# MPPT.net
KiCad netlist of a schematic drawn in EAGLE
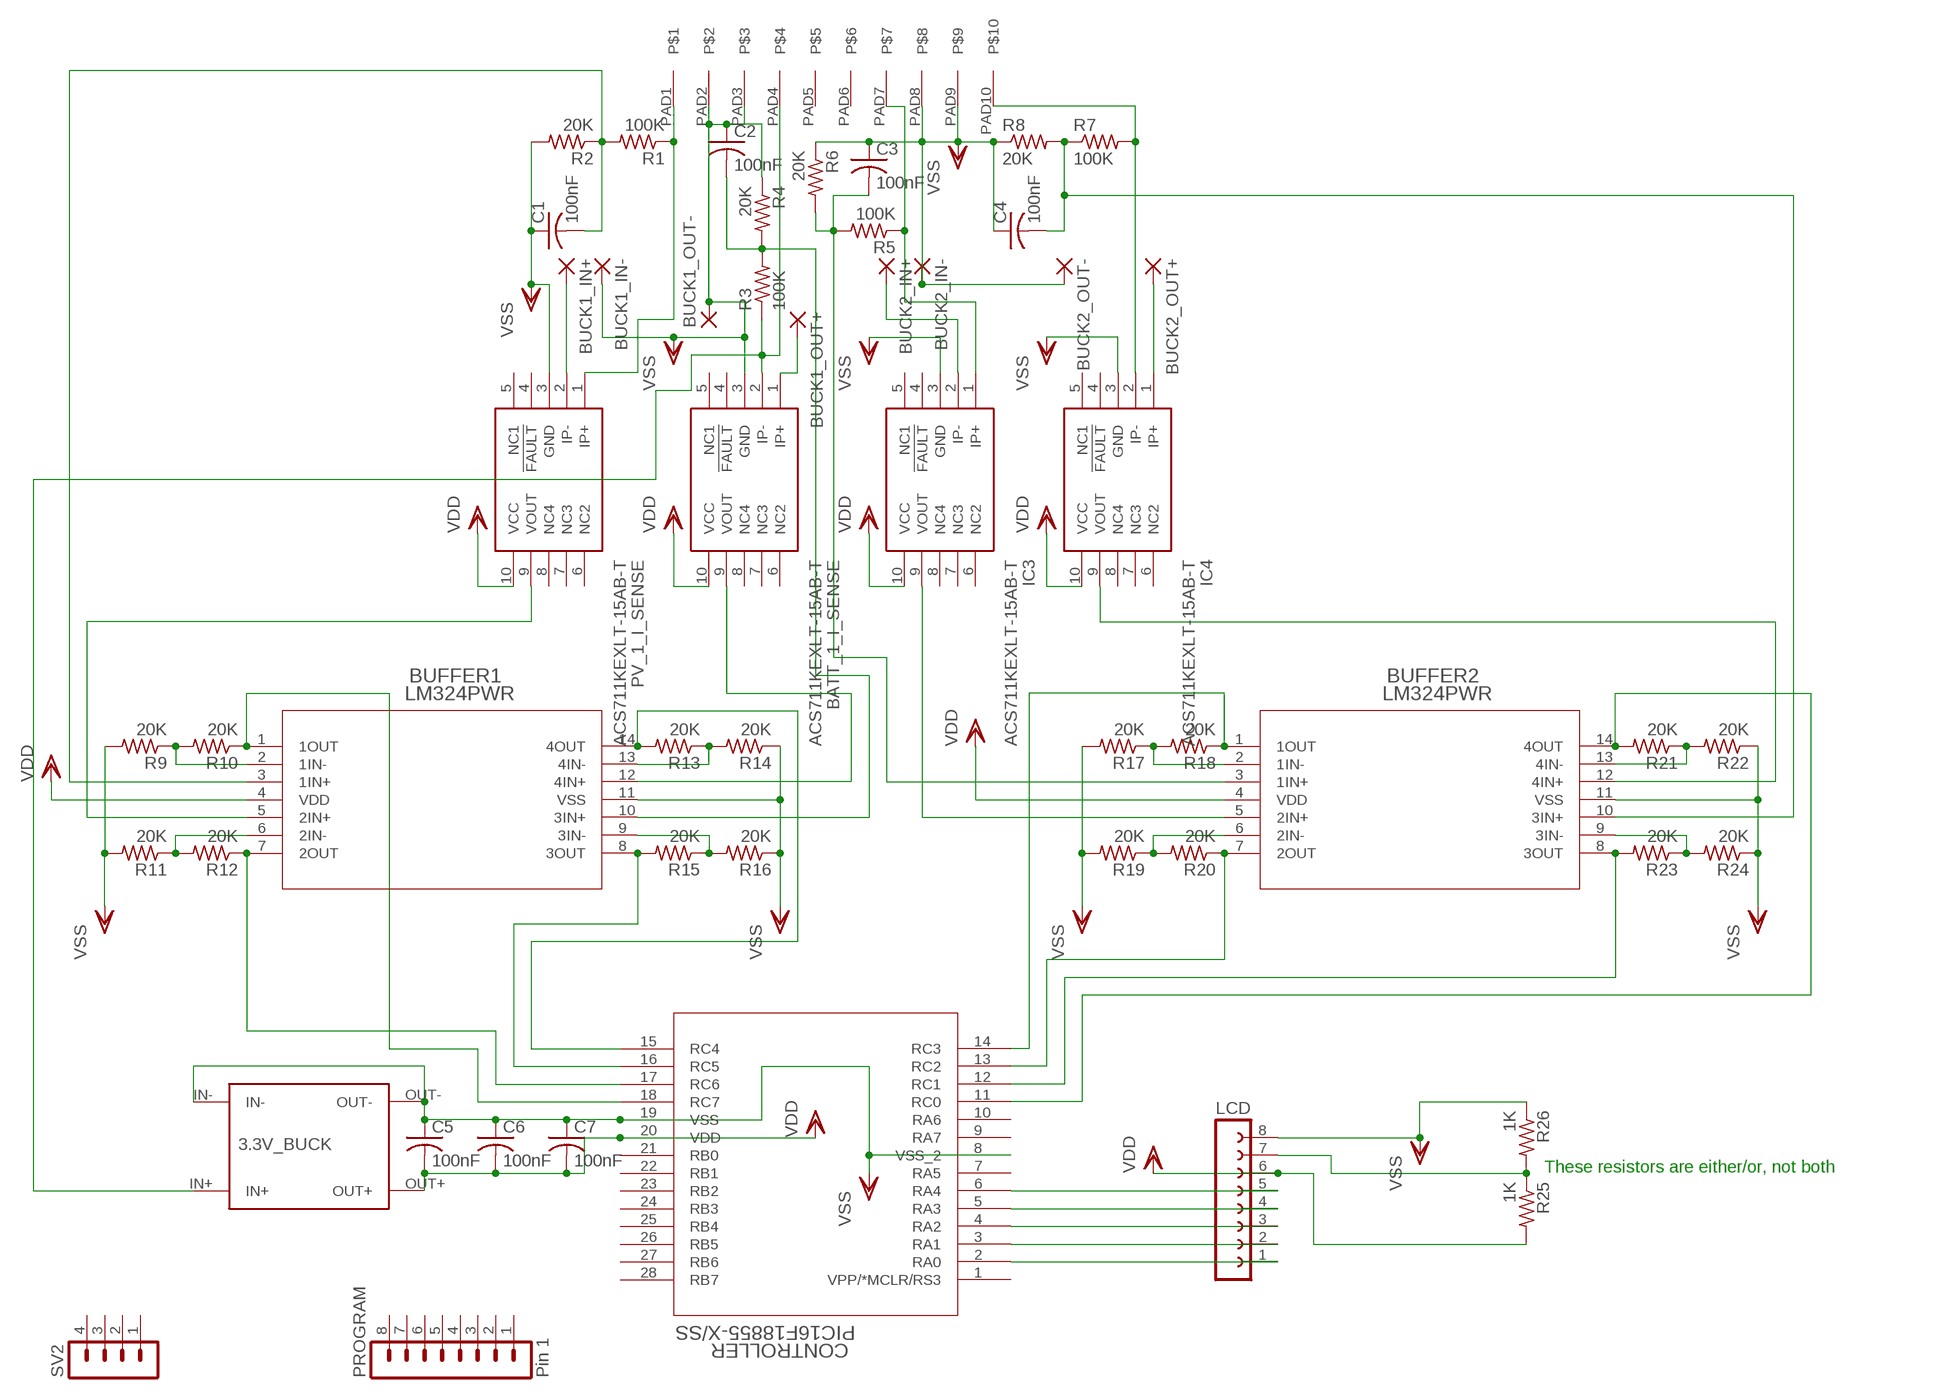
[diagram p0: schematic, sheet 1]

(export (version "E")
  (design (tool "Eeschema 10.0.6"))
  (components
    (comp (ref "3.3V_BUCK")
      (value "TINY_BUCK")
      (footprint "eagle-import:TINY_BUCK")
      (libsource (lib "eagle-import") (part "TINY_BUCK"))
    )
    (comp (ref "BATT_1_I_SENSE")
      (value "ACS711KEXLT-15AB-T")
      (footprint "eagle-import:EX-PACKAGE")
      (libsource (lib "eagle-import") (part "ACS711KEXLT-15AB-T"))
    )
    (comp (ref "BUCK1_IN+")
      (value "3,81/1,4")
      (footprint "eagle-import:3,81_1,4")
      (libsource (lib "eagle-import") (part "3,81/1,4"))
    )
    (comp (ref "BUCK1_IN-")
      (value "3,81/1,4")
      (footprint "eagle-import:3,81_1,4")
      (libsource (lib "eagle-import") (part "3,81/1,4"))
    )
    (comp (ref "BUCK1_OUT+")
      (value "3,81/1,4")
      (footprint "eagle-import:3,81_1,4")
      (libsource (lib "eagle-import") (part "3,81/1,4"))
    )
    (comp (ref "BUCK1_OUT-")
      (value "3,81/1,4")
      (footprint "eagle-import:3,81_1,4")
      (libsource (lib "eagle-import") (part "3,81/1,4"))
    )
    (comp (ref "BUCK2_IN+")
      (value "3,81/1,4")
      (footprint "eagle-import:3,81_1,4")
      (libsource (lib "eagle-import") (part "3,81/1,4"))
    )
    (comp (ref "BUCK2_IN-")
      (value "3,81/1,4")
      (footprint "eagle-import:3,81_1,4")
      (libsource (lib "eagle-import") (part "3,81/1,4"))
    )
    (comp (ref "BUCK2_OUT+")
      (value "3,81/1,4")
      (footprint "eagle-import:3,81_1,4")
      (libsource (lib "eagle-import") (part "3,81/1,4"))
    )
    (comp (ref "BUCK2_OUT-")
      (value "3,81/1,4")
      (footprint "eagle-import:3,81_1,4")
      (libsource (lib "eagle-import") (part "3,81/1,4"))
    )
    (comp (ref "BUFFER1")
      (value "LM324PWR")
      (footprint "eagle-import:PW14")
      (libsource (lib "eagle-import") (part "LM324PWR"))
    )
    (comp (ref "BUFFER2")
      (value "LM324PWR")
      (footprint "eagle-import:PW14")
      (libsource (lib "eagle-import") (part "LM324PWR"))
    )
    (comp (ref "C1")
      (value "100nF")
      (footprint "eagle-import:C0603")
      (libsource (lib "eagle-import") (part "C-USC0603"))
    )
    (comp (ref "C2")
      (value "100nF")
      (footprint "eagle-import:C0603")
      (libsource (lib "eagle-import") (part "C-USC0603"))
    )
    (comp (ref "C3")
      (value "100nF")
      (footprint "eagle-import:C0603")
      (libsource (lib "eagle-import") (part "C-USC0603"))
    )
    (comp (ref "C4")
      (value "100nF")
      (footprint "eagle-import:C0603")
      (libsource (lib "eagle-import") (part "C-USC0603"))
    )
    (comp (ref "C5")
      (value "100nF")
      (footprint "eagle-import:C0603")
      (libsource (lib "eagle-import") (part "C-USC0603"))
    )
    (comp (ref "C6")
      (value "100nF")
      (footprint "eagle-import:C0603")
      (libsource (lib "eagle-import") (part "C-USC0603"))
    )
    (comp (ref "C7")
      (value "100nF")
      (footprint "eagle-import:C0603")
      (libsource (lib "eagle-import") (part "C-USC0603"))
    )
    (comp (ref "CONTROLLER")
      (value "PIC16F18855-X/SS")
      (footprint "eagle-import:SSOP28_MC")
      (fields
        (field (name "MANUFACTURER_PART_NUMBER") "pic16f18855-x/ss")
        (field (name "COPYRIGHT") "Copyright (C) 2016 Accelerated Designs. All rights reserved")
      )
      (libsource (lib "eagle-import") (part "PIC16F18855-X/SS"))
    )
    (comp (ref "IC3")
      (value "ACS711KEXLT-15AB-T")
      (footprint "eagle-import:EX-PACKAGE")
      (libsource (lib "eagle-import") (part "ACS711KEXLT-15AB-T"))
    )
    (comp (ref "IC4")
      (value "ACS711KEXLT-15AB-T")
      (footprint "eagle-import:EX-PACKAGE")
      (libsource (lib "eagle-import") (part "ACS711KEXLT-15AB-T"))
    )
    (comp (ref "LCD")
      (value "FE08-1")
      (footprint "eagle-import:FE08")
      (libsource (lib "eagle-import") (part "FE08-1"))
    )
    (comp (ref "PROGRAM")
      (value "Pin 1")
      (footprint "eagle-import:MA08-1")
      (libsource (lib "eagle-import") (part "MA08-1"))
    )
    (comp (ref "PV_1_I_SENSE")
      (value "ACS711KEXLT-15AB-T")
      (footprint "eagle-import:EX-PACKAGE")
      (libsource (lib "eagle-import") (part "ACS711KEXLT-15AB-T"))
    )
    (comp (ref "R1")
      (value "100K")
      (footprint "eagle-import:R0603")
      (libsource (lib "eagle-import") (part "R-US_R0603"))
    )
    (comp (ref "R2")
      (value "20K")
      (footprint "eagle-import:R0603")
      (libsource (lib "eagle-import") (part "R-US_R0603"))
    )
    (comp (ref "R3")
      (value "100K")
      (footprint "eagle-import:R0603")
      (libsource (lib "eagle-import") (part "R-US_R0603"))
    )
    (comp (ref "R4")
      (value "20K")
      (footprint "eagle-import:R0603")
      (libsource (lib "eagle-import") (part "R-US_R0603"))
    )
    (comp (ref "R5")
      (value "100K")
      (footprint "eagle-import:R0603")
      (libsource (lib "eagle-import") (part "R-US_R0603"))
    )
    (comp (ref "R6")
      (value "20K")
      (footprint "eagle-import:R0603")
      (libsource (lib "eagle-import") (part "R-US_R0603"))
    )
    (comp (ref "R7")
      (value "100K")
      (footprint "eagle-import:R0603")
      (libsource (lib "eagle-import") (part "R-US_R0603"))
    )
    (comp (ref "R8")
      (value "20K")
      (footprint "eagle-import:R0603")
      (libsource (lib "eagle-import") (part "R-US_R0603"))
    )
    (comp (ref "R9")
      (value "20K")
      (footprint "eagle-import:R0603")
      (libsource (lib "eagle-import") (part "R-US_R0603"))
    )
    (comp (ref "R10")
      (value "20K")
      (footprint "eagle-import:R0603")
      (libsource (lib "eagle-import") (part "R-US_R0603"))
    )
    (comp (ref "R11")
      (value "20K")
      (footprint "eagle-import:R0603")
      (libsource (lib "eagle-import") (part "R-US_R0603"))
    )
    (comp (ref "R12")
      (value "20K")
      (footprint "eagle-import:R0603")
      (libsource (lib "eagle-import") (part "R-US_R0603"))
    )
    (comp (ref "R13")
      (value "20K")
      (footprint "eagle-import:R0603")
      (libsource (lib "eagle-import") (part "R-US_R0603"))
    )
    (comp (ref "R14")
      (value "20K")
      (footprint "eagle-import:R0603")
      (libsource (lib "eagle-import") (part "R-US_R0603"))
    )
    (comp (ref "R15")
      (value "20K")
      (footprint "eagle-import:R0603")
      (libsource (lib "eagle-import") (part "R-US_R0603"))
    )
    (comp (ref "R16")
      (value "20K")
      (footprint "eagle-import:R0603")
      (libsource (lib "eagle-import") (part "R-US_R0603"))
    )
    (comp (ref "R17")
      (value "20K")
      (footprint "eagle-import:R0603")
      (libsource (lib "eagle-import") (part "R-US_R0603"))
    )
    (comp (ref "R18")
      (value "20K")
      (footprint "eagle-import:R0603")
      (libsource (lib "eagle-import") (part "R-US_R0603"))
    )
    (comp (ref "R19")
      (value "20K")
      (footprint "eagle-import:R0603")
      (libsource (lib "eagle-import") (part "R-US_R0603"))
    )
    (comp (ref "R20")
      (value "20K")
      (footprint "eagle-import:R0603")
      (libsource (lib "eagle-import") (part "R-US_R0603"))
    )
    (comp (ref "R21")
      (value "20K")
      (footprint "eagle-import:R0603")
      (libsource (lib "eagle-import") (part "R-US_R0603"))
    )
    (comp (ref "R22")
      (value "20K")
      (footprint "eagle-import:R0603")
      (libsource (lib "eagle-import") (part "R-US_R0603"))
    )
    (comp (ref "R23")
      (value "20K")
      (footprint "eagle-import:R0603")
      (libsource (lib "eagle-import") (part "R-US_R0603"))
    )
    (comp (ref "R24")
      (value "20K")
      (footprint "eagle-import:R0603")
      (libsource (lib "eagle-import") (part "R-US_R0603"))
    )
    (comp (ref "R25")
      (value "1K")
      (footprint "eagle-import:R0603")
      (libsource (lib "eagle-import") (part "R-US_R0603"))
    )
    (comp (ref "R26")
      (value "1K")
      (footprint "eagle-import:R0603")
      (libsource (lib "eagle-import") (part "R-US_R0603"))
    )
    (comp (ref "SV2")
      (value "MA04-1")
      (footprint "eagle-import:MA04-1")
      (libsource (lib "eagle-import") (part "MA04-1"))
    )
    (comp (ref "U$1")
      (value "CONN-KF2EDG-10(5.08)E-BAYPLUGGABLECONNECTORS")
      (footprint "eagle-import:CONN-KF2EDG-10(5.08)")
      (libsource (lib "eagle-import") (part "CONN-KF2EDG-10(5.08)E-BAYPLUGGABLECONNECTORS"))
    )
  )
  (nets
    (net (code "1") (name "Net-(BATT_1_I_SENSE-IP+)") (class "Default")
      (node (ref "BATT_1_I_SENSE") (pin "1") (pinfunction "IP+_1") (pintype "bidirectional"))
      (node (ref "BUCK1_OUT+") (pin "1") (pinfunction "P_1") (pintype "passive"))
    )
    (net (code "2") (name "Net-(BATT_1_I_SENSE-IP-)") (class "Default")
      (node (ref "3.3V_BUCK") (pin "IN+") (pinfunction "IN+_IN+") (pintype "power_in"))
      (node (ref "BATT_1_I_SENSE") (pin "2") (pinfunction "IP-_2") (pintype "bidirectional"))
      (node (ref "R3") (pin "1") (pinfunction "1_1") (pintype "passive"))
      (node (ref "U$1") (pin "PAD4") (pinfunction "P$4_PAD4") (pintype "bidirectional"))
    )
    (net (code "3") (name "Net-(BATT_1_I_SENSE-VOUT)") (class "Default")
      (node (ref "BATT_1_I_SENSE") (pin "9") (pinfunction "VOUT_9") (pintype "bidirectional"))
      (node (ref "BUFFER1") (pin "12") (pinfunction "4IN+_12") (pintype "input"))
    )
    (net (code "4") (name "Net-(BUCK1_IN+-P)") (class "Default")
      (node (ref "BUCK1_IN+") (pin "1") (pinfunction "P_1") (pintype "passive"))
      (node (ref "PV_1_I_SENSE") (pin "2") (pinfunction "IP-_2") (pintype "bidirectional"))
    )
    (net (code "5") (name "Net-(BUCK2_IN+-P)") (class "Default")
      (node (ref "BUCK2_IN+") (pin "1") (pinfunction "P_1") (pintype "passive"))
      (node (ref "IC3") (pin "2") (pinfunction "IP-_2") (pintype "bidirectional"))
    )
    (net (code "6") (name "Net-(BUCK2_OUT+-P)") (class "Default")
      (node (ref "BUCK2_OUT+") (pin "1") (pinfunction "P_1") (pintype "passive"))
      (node (ref "IC4") (pin "1") (pinfunction "IP+_1") (pintype "bidirectional"))
    )
    (net (code "7") (name "Net-(BUFFER1-1IN+)") (class "Default")
      (node (ref "BUFFER1") (pin "3") (pinfunction "1IN+_3") (pintype "input"))
      (node (ref "C1") (pin "2") (pinfunction "2_2") (pintype "passive"))
      (node (ref "R1") (pin "2") (pinfunction "2_2") (pintype "passive"))
      (node (ref "R2") (pin "1") (pinfunction "1_1") (pintype "passive"))
    )
    (net (code "8") (name "Net-(BUFFER1-1IN-)") (class "Default")
      (node (ref "BUFFER1") (pin "2") (pinfunction "1IN-_2") (pintype "input"))
      (node (ref "R10") (pin "2") (pinfunction "2_2") (pintype "passive"))
      (node (ref "R9") (pin "1") (pinfunction "1_1") (pintype "passive"))
    )
    (net (code "9") (name "Net-(BUFFER1-1OUT)") (class "Default")
      (node (ref "BUFFER1") (pin "1") (pinfunction "1OUT_1") (pintype "output"))
      (node (ref "CONTROLLER") (pin "18") (pinfunction "RC7_18") (pintype "bidirectional"))
      (node (ref "R10") (pin "1") (pinfunction "1_1") (pintype "passive"))
    )
    (net (code "10") (name "Net-(BUFFER1-2IN+)") (class "Default")
      (node (ref "BUFFER1") (pin "5") (pinfunction "2IN+_5") (pintype "input"))
      (node (ref "PV_1_I_SENSE") (pin "9") (pinfunction "VOUT_9") (pintype "bidirectional"))
    )
    (net (code "11") (name "Net-(BUFFER1-2IN-)") (class "Default")
      (node (ref "BUFFER1") (pin "6") (pinfunction "2IN-_6") (pintype "input"))
      (node (ref "R11") (pin "1") (pinfunction "1_1") (pintype "passive"))
      (node (ref "R12") (pin "2") (pinfunction "2_2") (pintype "passive"))
    )
    (net (code "12") (name "Net-(BUFFER1-2OUT)") (class "Default")
      (node (ref "BUFFER1") (pin "7") (pinfunction "2OUT_7") (pintype "output"))
      (node (ref "CONTROLLER") (pin "17") (pinfunction "RC6_17") (pintype "bidirectional"))
      (node (ref "R12") (pin "1") (pinfunction "1_1") (pintype "passive"))
    )
    (net (code "13") (name "Net-(BUFFER1-3IN+)") (class "Default")
      (node (ref "BUFFER1") (pin "10") (pinfunction "3IN+_10") (pintype "input"))
      (node (ref "C2") (pin "2") (pinfunction "2_2") (pintype "passive"))
      (node (ref "R3") (pin "2") (pinfunction "2_2") (pintype "passive"))
      (node (ref "R4") (pin "2") (pinfunction "2_2") (pintype "passive"))
    )
    (net (code "14") (name "Net-(BUFFER1-3IN-)") (class "Default")
      (node (ref "BUFFER1") (pin "9") (pinfunction "3IN-_9") (pintype "input"))
      (node (ref "R15") (pin "1") (pinfunction "1_1") (pintype "passive"))
      (node (ref "R16") (pin "2") (pinfunction "2_2") (pintype "passive"))
    )
    (net (code "15") (name "Net-(BUFFER1-3OUT)") (class "Default")
      (node (ref "BUFFER1") (pin "8") (pinfunction "3OUT_8") (pintype "output"))
      (node (ref "CONTROLLER") (pin "16") (pinfunction "RC5_16") (pintype "bidirectional"))
      (node (ref "R15") (pin "2") (pinfunction "2_2") (pintype "passive"))
    )
    (net (code "16") (name "Net-(BUFFER1-4IN-)") (class "Default")
      (node (ref "BUFFER1") (pin "13") (pinfunction "4IN-_13") (pintype "input"))
      (node (ref "R13") (pin "1") (pinfunction "1_1") (pintype "passive"))
      (node (ref "R14") (pin "2") (pinfunction "2_2") (pintype "passive"))
    )
    (net (code "17") (name "Net-(BUFFER1-4OUT)") (class "Default")
      (node (ref "BUFFER1") (pin "14") (pinfunction "4OUT_14") (pintype "output"))
      (node (ref "CONTROLLER") (pin "15") (pinfunction "RC4_15") (pintype "bidirectional"))
      (node (ref "R13") (pin "2") (pinfunction "2_2") (pintype "passive"))
    )
    (net (code "18") (name "Net-(BUFFER2-1IN+)") (class "Default")
      (node (ref "BUFFER2") (pin "3") (pinfunction "1IN+_3") (pintype "input"))
      (node (ref "C3") (pin "2") (pinfunction "2_2") (pintype "passive"))
      (node (ref "R5") (pin "2") (pinfunction "2_2") (pintype "passive"))
      (node (ref "R6") (pin "2") (pinfunction "2_2") (pintype "passive"))
    )
    (net (code "19") (name "Net-(BUFFER2-1IN-)") (class "Default")
      (node (ref "BUFFER2") (pin "2") (pinfunction "1IN-_2") (pintype "input"))
      (node (ref "R17") (pin "1") (pinfunction "1_1") (pintype "passive"))
      (node (ref "R18") (pin "2") (pinfunction "2_2") (pintype "passive"))
    )
    (net (code "20") (name "Net-(BUFFER2-1OUT)") (class "Default")
      (node (ref "BUFFER2") (pin "1") (pinfunction "1OUT_1") (pintype "output"))
      (node (ref "CONTROLLER") (pin "14") (pinfunction "RC3_14") (pintype "bidirectional"))
      (node (ref "R18") (pin "1") (pinfunction "1_1") (pintype "passive"))
    )
    (net (code "21") (name "Net-(BUFFER2-2IN+)") (class "Default")
      (node (ref "BUFFER2") (pin "5") (pinfunction "2IN+_5") (pintype "input"))
      (node (ref "IC3") (pin "9") (pinfunction "VOUT_9") (pintype "bidirectional"))
    )
    (net (code "22") (name "Net-(BUFFER2-2IN-)") (class "Default")
      (node (ref "BUFFER2") (pin "6") (pinfunction "2IN-_6") (pintype "input"))
      (node (ref "R19") (pin "1") (pinfunction "1_1") (pintype "passive"))
      (node (ref "R20") (pin "2") (pinfunction "2_2") (pintype "passive"))
    )
    (net (code "23") (name "Net-(BUFFER2-2OUT)") (class "Default")
      (node (ref "BUFFER2") (pin "7") (pinfunction "2OUT_7") (pintype "output"))
      (node (ref "CONTROLLER") (pin "13") (pinfunction "RC2_13") (pintype "bidirectional"))
      (node (ref "R20") (pin "1") (pinfunction "1_1") (pintype "passive"))
    )
    (net (code "24") (name "Net-(BUFFER2-3IN+)") (class "Default")
      (node (ref "BUFFER2") (pin "10") (pinfunction "3IN+_10") (pintype "input"))
      (node (ref "C4") (pin "2") (pinfunction "2_2") (pintype "passive"))
      (node (ref "R7") (pin "1") (pinfunction "1_1") (pintype "passive"))
      (node (ref "R8") (pin "2") (pinfunction "2_2") (pintype "passive"))
    )
    (net (code "25") (name "Net-(BUFFER2-3IN-)") (class "Default")
      (node (ref "BUFFER2") (pin "9") (pinfunction "3IN-_9") (pintype "input"))
      (node (ref "R23") (pin "1") (pinfunction "1_1") (pintype "passive"))
      (node (ref "R24") (pin "2") (pinfunction "2_2") (pintype "passive"))
    )
    (net (code "26") (name "Net-(BUFFER2-3OUT)") (class "Default")
      (node (ref "BUFFER2") (pin "8") (pinfunction "3OUT_8") (pintype "output"))
      (node (ref "CONTROLLER") (pin "12") (pinfunction "RC1_12") (pintype "bidirectional"))
      (node (ref "R23") (pin "2") (pinfunction "2_2") (pintype "passive"))
    )
    (net (code "27") (name "Net-(BUFFER2-4IN+)") (class "Default")
      (node (ref "BUFFER2") (pin "12") (pinfunction "4IN+_12") (pintype "input"))
      (node (ref "IC4") (pin "9") (pinfunction "VOUT_9") (pintype "bidirectional"))
    )
    (net (code "28") (name "Net-(BUFFER2-4IN-)") (class "Default")
      (node (ref "BUFFER2") (pin "13") (pinfunction "4IN-_13") (pintype "input"))
      (node (ref "R21") (pin "1") (pinfunction "1_1") (pintype "passive"))
      (node (ref "R22") (pin "2") (pinfunction "2_2") (pintype "passive"))
    )
    (net (code "29") (name "Net-(BUFFER2-4OUT)") (class "Default")
      (node (ref "BUFFER2") (pin "14") (pinfunction "4OUT_14") (pintype "output"))
      (node (ref "CONTROLLER") (pin "11") (pinfunction "RC0_11") (pintype "bidirectional"))
      (node (ref "R21") (pin "2") (pinfunction "2_2") (pintype "passive"))
    )
    (net (code "30") (name "Net-(CONTROLLER-RA0)") (class "Default")
      (node (ref "CONTROLLER") (pin "2") (pinfunction "RA0_2") (pintype "bidirectional"))
      (node (ref "LCD") (pin "1") (pinfunction "1_1") (pintype "passive"))
    )
    (net (code "31") (name "Net-(CONTROLLER-RA1)") (class "Default")
      (node (ref "CONTROLLER") (pin "3") (pinfunction "RA1_3") (pintype "bidirectional"))
      (node (ref "LCD") (pin "2") (pinfunction "2_2") (pintype "passive"))
    )
    (net (code "32") (name "Net-(CONTROLLER-RA2)") (class "Default")
      (node (ref "CONTROLLER") (pin "4") (pinfunction "RA2_4") (pintype "bidirectional"))
      (node (ref "LCD") (pin "3") (pinfunction "3_3") (pintype "passive"))
    )
    (net (code "33") (name "Net-(CONTROLLER-RA3)") (class "Default")
      (node (ref "CONTROLLER") (pin "5") (pinfunction "RA3_5") (pintype "bidirectional"))
      (node (ref "LCD") (pin "4") (pinfunction "4_4") (pintype "passive"))
    )
    (net (code "34") (name "Net-(CONTROLLER-RA4)") (class "Default")
      (node (ref "CONTROLLER") (pin "6") (pinfunction "RA4_6") (pintype "bidirectional"))
      (node (ref "LCD") (pin "5") (pinfunction "5_5") (pintype "passive"))
    )
    (net (code "35") (name "Net-(IC3-IP+)") (class "Default")
      (node (ref "IC3") (pin "1") (pinfunction "IP+_1") (pintype "bidirectional"))
      (node (ref "R5") (pin "1") (pinfunction "1_1") (pintype "passive"))
      (node (ref "U$1") (pin "PAD7") (pinfunction "P$7_PAD7") (pintype "bidirectional"))
    )
    (net (code "36") (name "Net-(IC4-IP-)") (class "Default")
      (node (ref "IC4") (pin "2") (pinfunction "IP-_2") (pintype "bidirectional"))
      (node (ref "R7") (pin "2") (pinfunction "2_2") (pintype "passive"))
      (node (ref "U$1") (pin "PAD10") (pinfunction "P$10_PAD10") (pintype "bidirectional"))
    )
    (net (code "37") (name "Net-(LCD-Pad7)") (class "Default")
      (node (ref "LCD") (pin "7") (pinfunction "7_7") (pintype "passive"))
      (node (ref "R25") (pin "1") (pinfunction "1_1") (pintype "passive"))
      (node (ref "R26") (pin "2") (pinfunction "2_2") (pintype "passive"))
    )
    (net (code "38") (name "Net-(PV_1_I_SENSE-IP+)") (class "Default")
      (node (ref "PV_1_I_SENSE") (pin "1") (pinfunction "IP+_1") (pintype "bidirectional"))
      (node (ref "R1") (pin "1") (pinfunction "1_1") (pintype "passive"))
      (node (ref "U$1") (pin "PAD1") (pinfunction "P$1_PAD1") (pintype "bidirectional"))
    )
    (net (code "39") (name "VDD") (class "Default")
      (node (ref "3.3V_BUCK") (pin "OUT+") (pinfunction "OUT+_OUT+") (pintype "power_in"))
      (node (ref "BATT_1_I_SENSE") (pin "10") (pinfunction "VCC_10") (pintype "bidirectional"))
      (node (ref "BUFFER1") (pin "4") (pinfunction "VDD_4") (pintype "power_in"))
      (node (ref "BUFFER2") (pin "4") (pinfunction "VDD_4") (pintype "power_in"))
      (node (ref "C5") (pin "2") (pinfunction "2_2") (pintype "passive"))
      (node (ref "C6") (pin "2") (pinfunction "2_2") (pintype "passive"))
      (node (ref "C7") (pin "2") (pinfunction "2_2") (pintype "passive"))
      (node (ref "CONTROLLER") (pin "20") (pinfunction "VDD_20") (pintype "power_in"))
      (node (ref "IC3") (pin "10") (pinfunction "VCC_10") (pintype "bidirectional"))
      (node (ref "IC4") (pin "10") (pinfunction "VCC_10") (pintype "bidirectional"))
      (node (ref "LCD") (pin "6") (pinfunction "6_6") (pintype "passive"))
      (node (ref "PV_1_I_SENSE") (pin "10") (pinfunction "VCC_10") (pintype "bidirectional"))
      (node (ref "R25") (pin "2") (pinfunction "2_2") (pintype "passive"))
    )
    (net (code "40") (name "VSS") (class "Default")
      (node (ref "3.3V_BUCK") (pin "IN-") (pinfunction "IN-_IN-") (pintype "power_in"))
      (node (ref "3.3V_BUCK") (pin "OUT-") (pinfunction "OUT-_OUT-") (pintype "power_in"))
      (node (ref "BATT_1_I_SENSE") (pin "3") (pinfunction "GND_3") (pintype "bidirectional"))
      (node (ref "BUCK1_IN-") (pin "1") (pinfunction "P_1") (pintype "passive"))
      (node (ref "BUCK1_OUT-") (pin "1") (pinfunction "P_1") (pintype "passive"))
      (node (ref "BUCK2_IN-") (pin "1") (pinfunction "P_1") (pintype "passive"))
      (node (ref "BUCK2_OUT-") (pin "1") (pinfunction "P_1") (pintype "passive"))
      (node (ref "BUFFER1") (pin "11") (pinfunction "VSS_11") (pintype "power_in"))
      (node (ref "BUFFER2") (pin "11") (pinfunction "VSS_11") (pintype "power_in"))
      (node (ref "C1") (pin "1") (pinfunction "1_1") (pintype "passive"))
      (node (ref "C2") (pin "1") (pinfunction "1_1") (pintype "passive"))
      (node (ref "C3") (pin "1") (pinfunction "1_1") (pintype "passive"))
      (node (ref "C4") (pin "1") (pinfunction "1_1") (pintype "passive"))
      (node (ref "C5") (pin "1") (pinfunction "1_1") (pintype "passive"))
      (node (ref "C6") (pin "1") (pinfunction "1_1") (pintype "passive"))
      (node (ref "C7") (pin "1") (pinfunction "1_1") (pintype "passive"))
      (node (ref "CONTROLLER") (pin "19") (pinfunction "VSS_19") (pintype "power_in"))
      (node (ref "CONTROLLER") (pin "8") (pinfunction "VSS_2_8") (pintype "power_in"))
      (node (ref "IC3") (pin "3") (pinfunction "GND_3") (pintype "bidirectional"))
      (node (ref "IC4") (pin "3") (pinfunction "GND_3") (pintype "bidirectional"))
      (node (ref "LCD") (pin "8") (pinfunction "8_8") (pintype "passive"))
      (node (ref "PV_1_I_SENSE") (pin "3") (pinfunction "GND_3") (pintype "bidirectional"))
      (node (ref "R11") (pin "2") (pinfunction "2_2") (pintype "passive"))
      (node (ref "R14") (pin "1") (pinfunction "1_1") (pintype "passive"))
      (node (ref "R16") (pin "1") (pinfunction "1_1") (pintype "passive"))
      (node (ref "R17") (pin "2") (pinfunction "2_2") (pintype "passive"))
      (node (ref "R19") (pin "2") (pinfunction "2_2") (pintype "passive"))
      (node (ref "R2") (pin "2") (pinfunction "2_2") (pintype "passive"))
      (node (ref "R22") (pin "1") (pinfunction "1_1") (pintype "passive"))
      (node (ref "R24") (pin "1") (pinfunction "1_1") (pintype "passive"))
      (node (ref "R26") (pin "1") (pinfunction "1_1") (pintype "passive"))
      (node (ref "R4") (pin "1") (pinfunction "1_1") (pintype "passive"))
      (node (ref "R6") (pin "1") (pinfunction "1_1") (pintype "passive"))
      (node (ref "R8") (pin "1") (pinfunction "1_1") (pintype "passive"))
      (node (ref "R9") (pin "2") (pinfunction "2_2") (pintype "passive"))
      (node (ref "U$1") (pin "PAD2") (pinfunction "P$2_PAD2") (pintype "bidirectional"))
      (node (ref "U$1") (pin "PAD3") (pinfunction "P$3_PAD3") (pintype "bidirectional"))
      (node (ref "U$1") (pin "PAD8") (pinfunction "P$8_PAD8") (pintype "bidirectional"))
      (node (ref "U$1") (pin "PAD9") (pinfunction "P$9_PAD9") (pintype "bidirectional"))
    )
    (net (code "41") (name "unconnected-(BATT_1_I_SENSE-NC1-Pad5)") (class "Default")
      (node (ref "BATT_1_I_SENSE") (pin "5") (pinfunction "NC1_5") (pintype "bidirectional"))
    )
    (net (code "42") (name "unconnected-(BATT_1_I_SENSE-NC2-Pad6)") (class "Default")
      (node (ref "BATT_1_I_SENSE") (pin "6") (pinfunction "NC2_6") (pintype "bidirectional"))
    )
    (net (code "43") (name "unconnected-(BATT_1_I_SENSE-NC3-Pad7)") (class "Default")
      (node (ref "BATT_1_I_SENSE") (pin "7") (pinfunction "NC3_7") (pintype "bidirectional"))
    )
    (net (code "44") (name "unconnected-(BATT_1_I_SENSE-NC4-Pad8)") (class "Default")
      (node (ref "BATT_1_I_SENSE") (pin "8") (pinfunction "NC4_8") (pintype "bidirectional"))
    )
    (net (code "45") (name "unconnected-(BATT_1_I_SENSE-~{FAULT}-Pad4)") (class "Default")
      (node (ref "BATT_1_I_SENSE") (pin "4") (pinfunction "~{FAULT}_4") (pintype "bidirectional"))
    )
    (net (code "46") (name "unconnected-(CONTROLLER-RA5-Pad7)") (class "Default")
      (node (ref "CONTROLLER") (pin "7") (pinfunction "RA5_7") (pintype "bidirectional"))
    )
    (net (code "47") (name "unconnected-(CONTROLLER-RA6-Pad10)") (class "Default")
      (node (ref "CONTROLLER") (pin "10") (pinfunction "RA6_10") (pintype "bidirectional"))
    )
    (net (code "48") (name "unconnected-(CONTROLLER-RA7-Pad9)") (class "Default")
      (node (ref "CONTROLLER") (pin "9") (pinfunction "RA7_9") (pintype "bidirectional"))
    )
    (net (code "49") (name "unconnected-(CONTROLLER-RB0-Pad21)") (class "Default")
      (node (ref "CONTROLLER") (pin "21") (pinfunction "RB0_21") (pintype "bidirectional"))
    )
    (net (code "50") (name "unconnected-(CONTROLLER-RB1-Pad22)") (class "Default")
      (node (ref "CONTROLLER") (pin "22") (pinfunction "RB1_22") (pintype "bidirectional"))
    )
    (net (code "51") (name "unconnected-(CONTROLLER-RB2-Pad23)") (class "Default")
      (node (ref "CONTROLLER") (pin "23") (pinfunction "RB2_23") (pintype "bidirectional"))
    )
    (net (code "52") (name "unconnected-(CONTROLLER-RB3-Pad24)") (class "Default")
      (node (ref "CONTROLLER") (pin "24") (pinfunction "RB3_24") (pintype "bidirectional"))
    )
    (net (code "53") (name "unconnected-(CONTROLLER-RB4-Pad25)") (class "Default")
      (node (ref "CONTROLLER") (pin "25") (pinfunction "RB4_25") (pintype "bidirectional"))
    )
    (net (code "54") (name "unconnected-(CONTROLLER-RB5-Pad26)") (class "Default")
      (node (ref "CONTROLLER") (pin "26") (pinfunction "RB5_26") (pintype "bidirectional"))
    )
    (net (code "55") (name "unconnected-(CONTROLLER-RB6-Pad27)") (class "Default")
      (node (ref "CONTROLLER") (pin "27") (pinfunction "RB6_27") (pintype "bidirectional"))
    )
    (net (code "56") (name "unconnected-(CONTROLLER-RB7-Pad28)") (class "Default")
      (node (ref "CONTROLLER") (pin "28") (pinfunction "RB7_28") (pintype "bidirectional"))
    )
    (net (code "57") (name "unconnected-(CONTROLLER-VPP{slash}*MCLR{slash}RS3-Pad1)") (class "Default")
      (node (ref "CONTROLLER") (pin "1") (pinfunction "VPP/*MCLR/RS3_1") (pintype "bidirectional"))
    )
    (net (code "58") (name "unconnected-(IC3-NC1-Pad5)") (class "Default")
      (node (ref "IC3") (pin "5") (pinfunction "NC1_5") (pintype "bidirectional"))
    )
    (net (code "59") (name "unconnected-(IC3-NC2-Pad6)") (class "Default")
      (node (ref "IC3") (pin "6") (pinfunction "NC2_6") (pintype "bidirectional"))
    )
    (net (code "60") (name "unconnected-(IC3-NC3-Pad7)") (class "Default")
      (node (ref "IC3") (pin "7") (pinfunction "NC3_7") (pintype "bidirectional"))
    )
    (net (code "61") (name "unconnected-(IC3-NC4-Pad8)") (class "Default")
      (node (ref "IC3") (pin "8") (pinfunction "NC4_8") (pintype "bidirectional"))
    )
    (net (code "62") (name "unconnected-(IC3-~{FAULT}-Pad4)") (class "Default")
      (node (ref "IC3") (pin "4") (pinfunction "~{FAULT}_4") (pintype "bidirectional"))
    )
    (net (code "63") (name "unconnected-(IC4-NC1-Pad5)") (class "Default")
      (node (ref "IC4") (pin "5") (pinfunction "NC1_5") (pintype "bidirectional"))
    )
    (net (code "64") (name "unconnected-(IC4-NC2-Pad6)") (class "Default")
      (node (ref "IC4") (pin "6") (pinfunction "NC2_6") (pintype "bidirectional"))
    )
    (net (code "65") (name "unconnected-(IC4-NC3-Pad7)") (class "Default")
      (node (ref "IC4") (pin "7") (pinfunction "NC3_7") (pintype "bidirectional"))
    )
    (net (code "66") (name "unconnected-(IC4-NC4-Pad8)") (class "Default")
      (node (ref "IC4") (pin "8") (pinfunction "NC4_8") (pintype "bidirectional"))
    )
    (net (code "67") (name "unconnected-(IC4-~{FAULT}-Pad4)") (class "Default")
      (node (ref "IC4") (pin "4") (pinfunction "~{FAULT}_4") (pintype "bidirectional"))
    )
    (net (code "68") (name "unconnected-(PROGRAM-Pad1)") (class "Default")
      (node (ref "PROGRAM") (pin "1") (pinfunction "1_1") (pintype "passive"))
    )
    (net (code "69") (name "unconnected-(PROGRAM-Pad2)") (class "Default")
      (node (ref "PROGRAM") (pin "2") (pinfunction "2_2") (pintype "passive"))
    )
    (net (code "70") (name "unconnected-(PROGRAM-Pad3)") (class "Default")
      (node (ref "PROGRAM") (pin "3") (pinfunction "3_3") (pintype "passive"))
    )
    (net (code "71") (name "unconnected-(PROGRAM-Pad4)") (class "Default")
      (node (ref "PROGRAM") (pin "4") (pinfunction "4_4") (pintype "passive"))
    )
    (net (code "72") (name "unconnected-(PROGRAM-Pad5)") (class "Default")
      (node (ref "PROGRAM") (pin "5") (pinfunction "5_5") (pintype "passive"))
    )
    (net (code "73") (name "unconnected-(PROGRAM-Pad6)") (class "Default")
      (node (ref "PROGRAM") (pin "6") (pinfunction "6_6") (pintype "passive"))
    )
    (net (code "74") (name "unconnected-(PROGRAM-Pad7)") (class "Default")
      (node (ref "PROGRAM") (pin "7") (pinfunction "7_7") (pintype "passive"))
    )
    (net (code "75") (name "unconnected-(PROGRAM-Pad8)") (class "Default")
      (node (ref "PROGRAM") (pin "8") (pinfunction "8_8") (pintype "passive"))
    )
    (net (code "76") (name "unconnected-(PV_1_I_SENSE-NC1-Pad5)") (class "Default")
      (node (ref "PV_1_I_SENSE") (pin "5") (pinfunction "NC1_5") (pintype "bidirectional"))
    )
    (net (code "77") (name "unconnected-(PV_1_I_SENSE-NC2-Pad6)") (class "Default")
      (node (ref "PV_1_I_SENSE") (pin "6") (pinfunction "NC2_6") (pintype "bidirectional"))
    )
    (net (code "78") (name "unconnected-(PV_1_I_SENSE-NC3-Pad7)") (class "Default")
      (node (ref "PV_1_I_SENSE") (pin "7") (pinfunction "NC3_7") (pintype "bidirectional"))
    )
    (net (code "79") (name "unconnected-(PV_1_I_SENSE-NC4-Pad8)") (class "Default")
      (node (ref "PV_1_I_SENSE") (pin "8") (pinfunction "NC4_8") (pintype "bidirectional"))
    )
    (net (code "80") (name "unconnected-(PV_1_I_SENSE-~{FAULT}-Pad4)") (class "Default")
      (node (ref "PV_1_I_SENSE") (pin "4") (pinfunction "~{FAULT}_4") (pintype "bidirectional"))
    )
    (net (code "81") (name "unconnected-(SV2-Pad1)") (class "Default")
      (node (ref "SV2") (pin "1") (pinfunction "1_1") (pintype "passive"))
    )
    (net (code "82") (name "unconnected-(SV2-Pad2)") (class "Default")
      (node (ref "SV2") (pin "2") (pinfunction "2_2") (pintype "passive"))
    )
    (net (code "83") (name "unconnected-(SV2-Pad3)") (class "Default")
      (node (ref "SV2") (pin "3") (pinfunction "3_3") (pintype "passive"))
    )
    (net (code "84") (name "unconnected-(SV2-Pad4)") (class "Default")
      (node (ref "SV2") (pin "4") (pinfunction "4_4") (pintype "passive"))
    )
    (net (code "85") (name "unconnected-(U$1-P$5-PadPAD5)") (class "Default")
      (node (ref "U$1") (pin "PAD5") (pinfunction "P$5_PAD5") (pintype "bidirectional"))
    )
    (net (code "86") (name "unconnected-(U$1-P$6-PadPAD6)") (class "Default")
      (node (ref "U$1") (pin "PAD6") (pinfunction "P$6_PAD6") (pintype "bidirectional"))
    )
  )
)
